# LinearActuator_SCH.net
KiCad netlist of a schematic drawn in Altium Designer
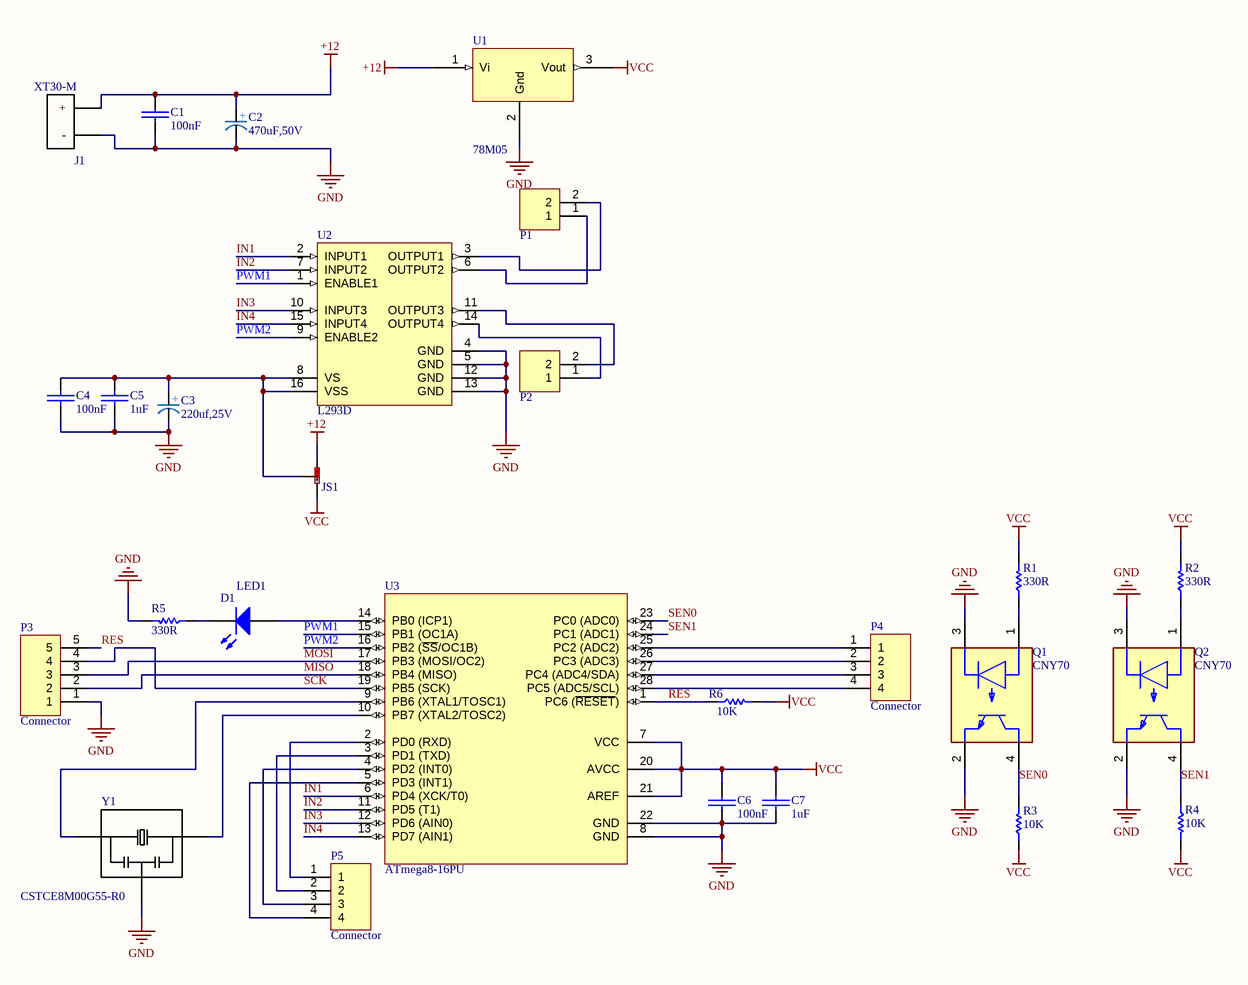
[diagram p0: LinearActuator_SCH.SchDoc]

(export (version "E")
  (design (tool "Eeschema 10.0.6"))
  (components
    (comp (ref "C1")
      (value "100nF")
      (footprint "SMD_CAP_0603")
      (description "Bipolar Capacitor")
      (fields (field (name "VOLTAGE") "100V") (field (name "DESIGNER") "Saeid Jorablo"))
      (libsource (lib "R2T Team Library") (part "Cap-Bipolar"))
    )
    (comp (ref "C2")
      (value "470uF,50V")
      (footprint "CAPE R3.5")
      (fields (field (name "DESIGNER") "Hamed Jafarzadeh ( R2T )"))
      (libsource (lib "R2T Team Library") (part "Capacitor Polarized"))
    )
    (comp (ref "C3")
      (value "220uf,25V")
      (footprint "CAPE R3.5")
      (fields (field (name "DESIGNER") "Hamed Jafarzadeh ( R2T )"))
      (libsource (lib "R2T Team Library") (part "Capacitor Polarized"))
    )
    (comp (ref "C4")
      (value "100nF")
      (footprint "SMD_CAP_0603")
      (description "Bipolar Capacitor")
      (fields (field (name "VOLTAGE") "100V") (field (name "DESIGNER") "Saeid Jorablo"))
      (libsource (lib "R2T Team Library") (part "Cap-Bipolar"))
    )
    (comp (ref "C5")
      (value "1uF")
      (footprint "SMD_CAP_0603")
      (description "Bipolar Capacitor")
      (fields (field (name "VOLTAGE") "100V") (field (name "DESIGNER") "Saeid Jorablo"))
      (libsource (lib "R2T Team Library") (part "Cap-Bipolar"))
    )
    (comp (ref "C6")
      (value "100nF")
      (footprint "SMD_CAP_0603")
      (description "Bipolar Capacitor")
      (fields (field (name "VOLTAGE") "100V") (field (name "DESIGNER") "Saeid Jorablo"))
      (libsource (lib "R2T Team Library") (part "Cap-Bipolar"))
    )
    (comp (ref "C7")
      (value "1uF")
      (footprint "SMD_CAP_0603")
      (description "Bipolar Capacitor")
      (fields (field (name "VOLTAGE") "100V") (field (name "DESIGNER") "Saeid Jorablo"))
      (libsource (lib "R2T Team Library") (part "Cap-Bipolar"))
    )
    (comp (ref "D1")
      (value "LED1")
      (footprint "LED-1")
      (description "Typical RED GaAs LED")
      (fields (field (name "PUBLISHER") "Altium Limited"))
      (libsource (lib "Miscellaneous Devices") (part "LED1"))
    )
    (comp (ref "J1")
      (value "XT30-M")
      (footprint "XT30-M side")
      (fields (field (name "MP") "XT60-M") (field (name "MF") "AMASS"))
      (libsource (lib "lib") (part "XT30-M"))
    )
    (comp (ref "JS1")
      (value "JumperSMD 3Pin")
      (footprint "JumperSMD 3Pin")
      (libsource (lib "R2T Team Library") (part "JumperSMD 3Pin"))
    )
    (comp (ref "P1")
      (value "Connector")
      (footprint "PH Connector 2Pin")
      (fields (field (name "DESIGNER:") "Hamed Jafarzadeh - www.R2T.ir"))
      (libsource (lib "R2T Team Library") (part "Connector 2Pin"))
    )
    (comp (ref "P2")
      (value "Connector")
      (footprint "PH Connector 2Pin")
      (fields (field (name "DESIGNER:") "Hamed Jafarzadeh - www.R2T.ir"))
      (libsource (lib "R2T Team Library") (part "Connector 2Pin"))
    )
    (comp (ref "P3")
      (value "Connector")
      (footprint "Polarized Header 5")
      (fields (field (name "DESIGNER:") "Hamed Jafarzadeh - www.R2T.ir"))
      (libsource (lib "R2T Team Library") (part "Connector 5Pin"))
    )
    (comp (ref "P4")
      (value "Connector")
      (footprint "Polarized Header 4")
      (fields (field (name "DESIGNER:") "Hamed Jafarzadeh - www.R2T.ir"))
      (libsource (lib "R2T Team Library") (part "Connector 4Pin"))
    )
    (comp (ref "P5")
      (value "Connector")
      (footprint "Polarized Header 4")
      (fields (field (name "DESIGNER:") "Hamed Jafarzadeh - www.R2T.ir"))
      (libsource (lib "R2T Team Library") (part "Connector 4Pin"))
    )
    (comp (ref "Q1")
      (value "CNY70")
      (footprint "FP-6_544-5062_01-4-MFG")
      (description "SENSOR OPTO TRANS 5MM REFLTH PCB")
      (fields
        (field (name "MANUFACTURER") "Vishay Semiconductor Opto Division")
        (field (name "OCTOPART") "https://octopart.com/cny70-vishay-39692873")
      )
      (libsource (lib "Altium Content Vault") (part "76cf3928268f24b4c386281b57b36cb"))
    )
    (comp (ref "Q2")
      (value "CNY70")
      (footprint "FP-6_544-5062_01-4-MFG")
      (description "SENSOR OPTO TRANS 5MM REFLTH PCB")
      (fields
        (field (name "MANUFACTURER") "Vishay Semiconductor Opto Division")
        (field (name "OCTOPART") "https://octopart.com/cny70-vishay-39692873")
      )
      (libsource (lib "Altium Content Vault") (part "76cf3928268f24b4c386281b57b36cb"))
    )
    (comp (ref "R1")
      (value "330R")
      (footprint "Res-(1/4)")
      (description "Resistor")
      (fields (field (name "TOLERANCE") "5%") (field (name "POWER") "1/8 W"))
      (libsource (lib "R2T Team Library") (part "Resistor"))
    )
    (comp (ref "R2")
      (value "330R")
      (footprint "Res-(1/4)")
      (description "Resistor")
      (fields (field (name "TOLERANCE") "5%") (field (name "POWER") "1/8 W"))
      (libsource (lib "R2T Team Library") (part "Resistor"))
    )
    (comp (ref "R3")
      (value "10K")
      (footprint "Res-(1/4)")
      (description "Resistor")
      (fields (field (name "TOLERANCE") "5%") (field (name "POWER") "1/8 W"))
      (libsource (lib "R2T Team Library") (part "Resistor"))
    )
    (comp (ref "R4")
      (value "10K")
      (footprint "Res-(1/4)")
      (description "Resistor")
      (fields (field (name "TOLERANCE") "5%") (field (name "POWER") "1/8 W"))
      (libsource (lib "R2T Team Library") (part "Resistor"))
    )
    (comp (ref "R5")
      (value "330R")
      (footprint "Res-(1/4)")
      (description "Resistor")
      (fields (field (name "TOLERANCE") "5%") (field (name "POWER") "1/8 W"))
      (libsource (lib "R2T Team Library") (part "Resistor"))
    )
    (comp (ref "R6")
      (value "10K")
      (footprint "Res-(1/4)")
      (description "Resistor")
      (fields (field (name "TOLERANCE") "5%") (field (name "POWER") "1/8 W"))
      (libsource (lib "R2T Team Library") (part "Resistor"))
    )
    (comp (ref "U1")
      (value "78M05")
      (footprint "TO220-AB-Stand")
      (libsource (lib "R2T Team Library") (part "Regulator"))
    )
    (comp (ref "U2")
      (value "L293D")
      (footprint "STM-L293D-16")
      (description "Push-Pull Four Channel Driver with Diode, 4.5 to 36 V, -40 to 150 degC, 16-Pin PDIP, RoHS, Tube")
      (fields (field (name "MANUFACTURER") "STMicroelectronics"))
      (libsource (lib "Altium Content Vault") (part "STM-L293D-16"))
    )
    (comp (ref "U3")
      (value "ATmega8-16PU")
      (footprint "28P3")
      (libsource (lib "Altium Content Vault") (part "MC-8B-AT8L-IL28"))
    )
    (comp (ref "Y1")
      (value "CSTCE8M00G55-R0")
      (footprint "*OSC_CSTCE8M00G55-R0")
      (description "Ceramic Resonator 8MHz ??0.5% _Tol_ ??0.2% _Stability_ 33pF 40Ohm 3-Pin CSMD T/R")
      (fields (field (name "MF") "Murata"))
      (libsource (lib "lib") (part "CSTCE8M00G55-R0"))
    )
  )
  (nets
    (net (code "1") (name "+12") (class "Default")
      (node (ref "C1") (pin "1") (pinfunction "+_1") (pintype "passive"))
      (node (ref "C2") (pin "1") (pintype "passive"))
      (node (ref "J1") (pin "PLUS") (pinfunction "+_PLUS") (pintype "passive"))
      (node (ref "JS1") (pin "3") (pintype "passive"))
      (node (ref "U1") (pin "1") (pinfunction "Vi_1") (pintype "input"))
    )
    (net (code "2") (name "/IN1") (class "Default")
      (node (ref "U2") (pin "2") (pinfunction "INPUT1_2") (pintype "input"))
      (node (ref "U3") (pin "6") (pinfunction "PD4_(XCK/T0)_6") (pintype "bidirectional"))
    )
    (net (code "3") (name "/IN2") (class "Default")
      (node (ref "U2") (pin "7") (pinfunction "INPUT2_7") (pintype "input"))
      (node (ref "U3") (pin "11") (pinfunction "PD5_(T1)_11") (pintype "bidirectional"))
    )
    (net (code "4") (name "/IN3") (class "Default")
      (node (ref "U2") (pin "10") (pinfunction "INPUT3_10") (pintype "input"))
      (node (ref "U3") (pin "12") (pinfunction "PD6_(AIN0)_12") (pintype "bidirectional"))
    )
    (net (code "5") (name "/IN4") (class "Default")
      (node (ref "U2") (pin "15") (pinfunction "INPUT4_15") (pintype "input"))
      (node (ref "U3") (pin "13") (pinfunction "PD7_(AIN1)_13") (pintype "bidirectional"))
    )
    (net (code "6") (name "/MISO") (class "Default")
      (node (ref "P3") (pin "2") (pinfunction "2_2") (pintype "passive"))
      (node (ref "U3") (pin "18") (pinfunction "PB4_(MISO)_18") (pintype "bidirectional"))
    )
    (net (code "7") (name "/MOSI") (class "Default")
      (node (ref "P3") (pin "3") (pinfunction "3_3") (pintype "passive"))
      (node (ref "U3") (pin "17") (pinfunction "PB3_(MOSI/OC2)_17") (pintype "bidirectional"))
    )
    (net (code "8") (name "/PWM1") (class "Default")
      (node (ref "U2") (pin "1") (pinfunction "ENABLE1_1") (pintype "input"))
      (node (ref "U3") (pin "15") (pinfunction "PB1_(OC1A)_15") (pintype "bidirectional"))
    )
    (net (code "9") (name "/PWM2") (class "Default")
      (node (ref "U2") (pin "9") (pinfunction "ENABLE2_9") (pintype "input"))
      (node (ref "U3") (pin "16") (pinfunction "PB2_(~{SS}/OC1B)_16") (pintype "bidirectional"))
    )
    (net (code "10") (name "/RES") (class "Default")
      (node (ref "P3") (pin "5") (pinfunction "5_5") (pintype "passive"))
      (node (ref "R6") (pin "1") (pinfunction "1_1") (pintype "passive"))
      (node (ref "U3") (pin "1") (pinfunction "PC6_(~{RESET})_1") (pintype "bidirectional"))
    )
    (net (code "11") (name "/SCK") (class "Default")
      (node (ref "P3") (pin "4") (pinfunction "4_4") (pintype "passive"))
      (node (ref "U3") (pin "19") (pinfunction "PB5_(SCK)_19") (pintype "bidirectional"))
    )
    (net (code "12") (name "/SEN0") (class "Default")
      (node (ref "Q1") (pin "4") (pinfunction "C_4") (pintype "passive"))
      (node (ref "R3") (pin "2") (pinfunction "2_2") (pintype "passive"))
      (node (ref "U3") (pin "23") (pinfunction "PC0_(ADC0)_23") (pintype "bidirectional"))
    )
    (net (code "13") (name "/SEN1") (class "Default")
      (node (ref "Q2") (pin "4") (pinfunction "C_4") (pintype "passive"))
      (node (ref "R4") (pin "1") (pinfunction "1_1") (pintype "passive"))
      (node (ref "U3") (pin "24") (pinfunction "PC1_(ADC1)_24") (pintype "bidirectional"))
    )
    (net (code "14") (name "GND") (class "Default")
      (node (ref "C1") (pin "2") (pinfunction "-_2") (pintype "passive"))
      (node (ref "C2") (pin "2") (pintype "passive"))
      (node (ref "C3") (pin "2") (pintype "passive"))
      (node (ref "C4") (pin "2") (pinfunction "-_2") (pintype "passive"))
      (node (ref "C5") (pin "2") (pinfunction "-_2") (pintype "passive"))
      (node (ref "C6") (pin "2") (pinfunction "-_2") (pintype "passive"))
      (node (ref "C7") (pin "2") (pinfunction "-_2") (pintype "passive"))
      (node (ref "J1") (pin "MINUS") (pinfunction "-_MINUS") (pintype "passive"))
      (node (ref "P3") (pin "1") (pinfunction "1_1") (pintype "passive"))
      (node (ref "Q1") (pin "2") (pinfunction "E_2") (pintype "passive"))
      (node (ref "Q1") (pin "3") (pinfunction "C_3") (pintype "passive"))
      (node (ref "Q2") (pin "2") (pinfunction "E_2") (pintype "passive"))
      (node (ref "Q2") (pin "3") (pinfunction "C_3") (pintype "passive"))
      (node (ref "R5") (pin "2") (pinfunction "2_2") (pintype "passive"))
      (node (ref "U1") (pin "2") (pinfunction "Gnd_2") (pintype "passive"))
      (node (ref "U2") (pin "12") (pinfunction "GND_12") (pintype "power_in"))
      (node (ref "U2") (pin "13") (pinfunction "GND_13") (pintype "power_in"))
      (node (ref "U2") (pin "4") (pinfunction "GND_4") (pintype "power_in"))
      (node (ref "U2") (pin "5") (pinfunction "GND_5") (pintype "power_in"))
      (node (ref "U3") (pin "22") (pinfunction "GND_22") (pintype "power_in"))
      (node (ref "U3") (pin "8") (pinfunction "GND_8") (pintype "power_in"))
      (node (ref "Y1") (pin "2") (pinfunction "2_2") (pintype "power_in"))
    )
    (net (code "15") (name "Net-(C4-+)") (class "Default")
      (node (ref "C3") (pin "1") (pintype "passive"))
      (node (ref "C4") (pin "1") (pinfunction "+_1") (pintype "passive"))
      (node (ref "C5") (pin "1") (pinfunction "+_1") (pintype "passive"))
      (node (ref "JS1") (pin "2") (pintype "passive"))
      (node (ref "U2") (pin "16") (pinfunction "VSS_16") (pintype "power_in"))
      (node (ref "U2") (pin "8") (pinfunction "VS_8") (pintype "power_in"))
    )
    (net (code "16") (name "Net-(D1-A)") (class "Default")
      (node (ref "D1") (pin "1") (pinfunction "A_1") (pintype "passive"))
      (node (ref "U3") (pin "14") (pinfunction "PB0_(ICP1)_14") (pintype "bidirectional"))
    )
    (net (code "17") (name "Net-(D1-K)") (class "Default")
      (node (ref "D1") (pin "2") (pinfunction "K_2") (pintype "passive"))
      (node (ref "R5") (pin "1") (pinfunction "1_1") (pintype "passive"))
    )
    (net (code "18") (name "Net-(Q1-A)") (class "Default")
      (node (ref "Q1") (pin "1") (pinfunction "A_1") (pintype "passive"))
      (node (ref "R1") (pin "1") (pinfunction "1_1") (pintype "passive"))
    )
    (net (code "19") (name "Net-(Q2-A)") (class "Default")
      (node (ref "Q2") (pin "1") (pinfunction "A_1") (pintype "passive"))
      (node (ref "R2") (pin "1") (pinfunction "1_1") (pintype "passive"))
    )
    (net (code "20") (name "Net-(U2-OUTPUT1)") (class "Default")
      (node (ref "P1") (pin "2") (pinfunction "2_2") (pintype "passive"))
      (node (ref "U2") (pin "3") (pinfunction "OUTPUT1_3") (pintype "output"))
    )
    (net (code "21") (name "Net-(U2-OUTPUT2)") (class "Default")
      (node (ref "P1") (pin "1") (pinfunction "1_1") (pintype "passive"))
      (node (ref "U2") (pin "6") (pinfunction "OUTPUT2_6") (pintype "output"))
    )
    (net (code "22") (name "Net-(U2-OUTPUT3)") (class "Default")
      (node (ref "P2") (pin "2") (pinfunction "2_2") (pintype "passive"))
      (node (ref "U2") (pin "11") (pinfunction "OUTPUT3_11") (pintype "output"))
    )
    (net (code "23") (name "Net-(U2-OUTPUT4)") (class "Default")
      (node (ref "P2") (pin "1") (pinfunction "1_1") (pintype "passive"))
      (node (ref "U2") (pin "14") (pinfunction "OUTPUT4_14") (pintype "output"))
    )
    (net (code "24") (name "Net-(U3-PB6_(XTAL1{slash}TOSC1))") (class "Default")
      (node (ref "U3") (pin "9") (pinfunction "PB6_(XTAL1/TOSC1)_9") (pintype "bidirectional"))
      (node (ref "Y1") (pin "1") (pinfunction "1_1") (pintype "passive"))
    )
    (net (code "25") (name "Net-(U3-PB7_(XTAL2{slash}TOSC2))") (class "Default")
      (node (ref "U3") (pin "10") (pinfunction "PB7_(XTAL2/TOSC2)_10") (pintype "bidirectional"))
      (node (ref "Y1") (pin "3") (pinfunction "3_3") (pintype "passive"))
    )
    (net (code "26") (name "Net-(U3-PC2_(ADC2))") (class "Default")
      (node (ref "P4") (pin "1") (pinfunction "1_1") (pintype "passive"))
      (node (ref "U3") (pin "25") (pinfunction "PC2_(ADC2)_25") (pintype "bidirectional"))
    )
    (net (code "27") (name "Net-(U3-PC3_(ADC3))") (class "Default")
      (node (ref "P4") (pin "2") (pinfunction "2_2") (pintype "passive"))
      (node (ref "U3") (pin "26") (pinfunction "PC3_(ADC3)_26") (pintype "bidirectional"))
    )
    (net (code "28") (name "Net-(U3-PC4_(ADC4{slash}SDA))") (class "Default")
      (node (ref "P4") (pin "3") (pinfunction "3_3") (pintype "passive"))
      (node (ref "U3") (pin "27") (pinfunction "PC4_(ADC4/SDA)_27") (pintype "bidirectional"))
    )
    (net (code "29") (name "Net-(U3-PC5_(ADC5{slash}SCL))") (class "Default")
      (node (ref "P4") (pin "4") (pinfunction "4_4") (pintype "passive"))
      (node (ref "U3") (pin "28") (pinfunction "PC5_(ADC5/SCL)_28") (pintype "bidirectional"))
    )
    (net (code "30") (name "Net-(U3-PD0_(RXD))") (class "Default")
      (node (ref "P5") (pin "1") (pinfunction "1_1") (pintype "passive"))
      (node (ref "U3") (pin "2") (pinfunction "PD0_(RXD)_2") (pintype "bidirectional"))
    )
    (net (code "31") (name "Net-(U3-PD1_(TXD))") (class "Default")
      (node (ref "P5") (pin "2") (pinfunction "2_2") (pintype "passive"))
      (node (ref "U3") (pin "3") (pinfunction "PD1_(TXD)_3") (pintype "bidirectional"))
    )
    (net (code "32") (name "Net-(U3-PD2_(INT0))") (class "Default")
      (node (ref "P5") (pin "3") (pinfunction "3_3") (pintype "passive"))
      (node (ref "U3") (pin "4") (pinfunction "PD2_(INT0)_4") (pintype "bidirectional"))
    )
    (net (code "33") (name "Net-(U3-PD3_(INT1))") (class "Default")
      (node (ref "P5") (pin "4") (pinfunction "4_4") (pintype "passive"))
      (node (ref "U3") (pin "5") (pinfunction "PD3_(INT1)_5") (pintype "bidirectional"))
    )
    (net (code "34") (name "VCC") (class "Default")
      (node (ref "C6") (pin "1") (pinfunction "+_1") (pintype "passive"))
      (node (ref "C7") (pin "1") (pinfunction "+_1") (pintype "passive"))
      (node (ref "JS1") (pin "1") (pintype "passive"))
      (node (ref "R1") (pin "2") (pinfunction "2_2") (pintype "passive"))
      (node (ref "R2") (pin "2") (pinfunction "2_2") (pintype "passive"))
      (node (ref "R3") (pin "1") (pinfunction "1_1") (pintype "passive"))
      (node (ref "R4") (pin "2") (pinfunction "2_2") (pintype "passive"))
      (node (ref "R6") (pin "2") (pinfunction "2_2") (pintype "passive"))
      (node (ref "U1") (pin "3") (pinfunction "Vout_3") (pintype "output"))
      (node (ref "U3") (pin "20") (pinfunction "AVCC_20") (pintype "power_in"))
      (node (ref "U3") (pin "21") (pinfunction "AREF_21") (pintype "passive"))
      (node (ref "U3") (pin "7") (pinfunction "VCC_7") (pintype "power_in"))
    )
  )
)
